# pressure-balloon.net
KiCad netlist of a schematic drawn in EAGLE
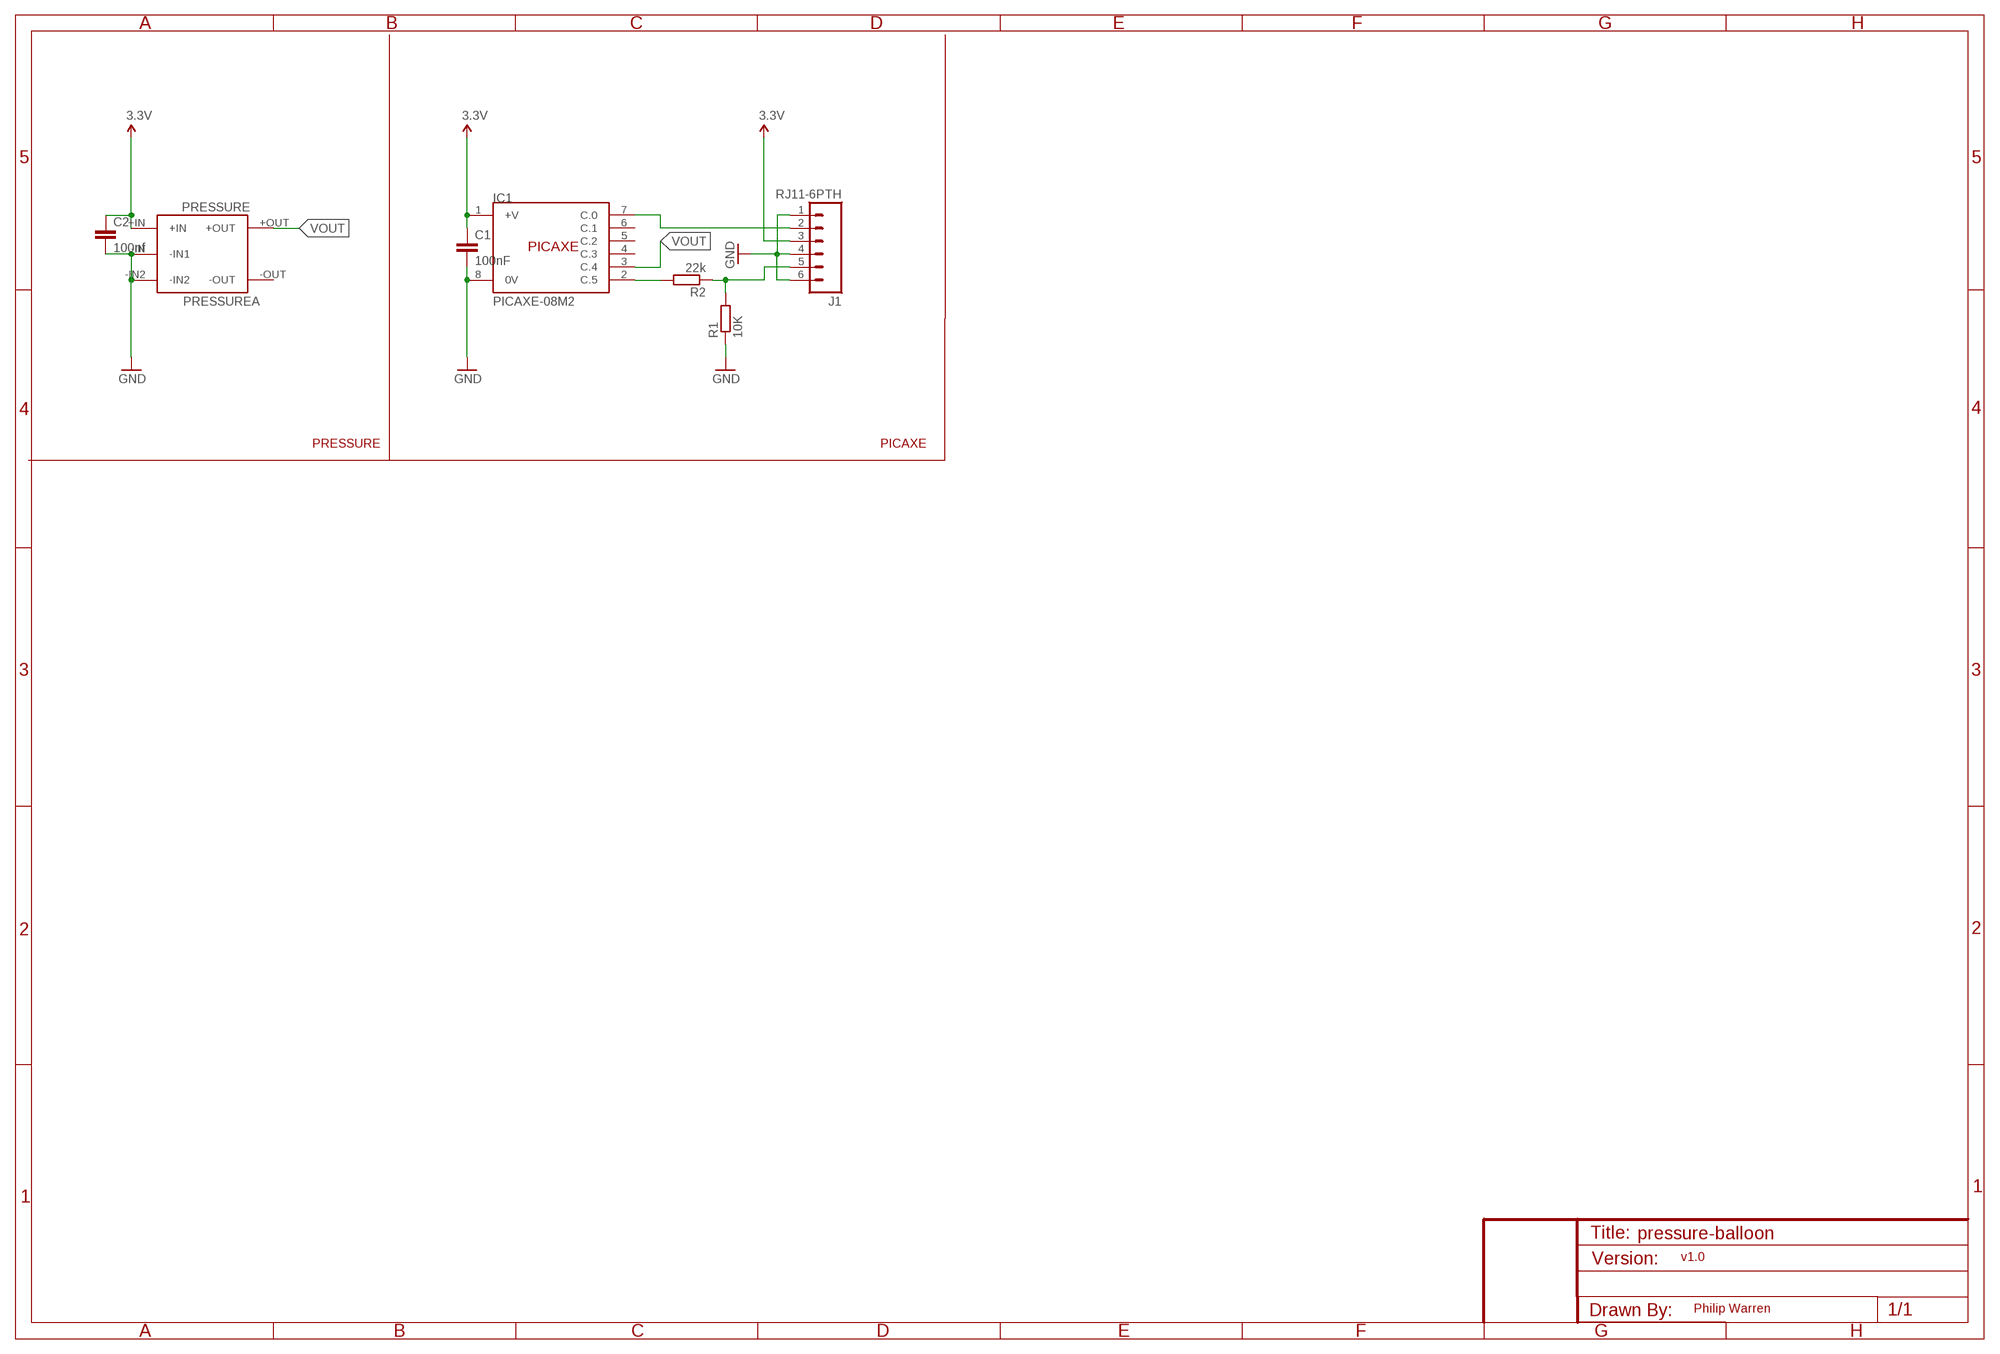
[diagram p0: schematic, sheet 1]

(export (version "E")
  (design (tool "Eeschema 10.0.6"))
  (components
    (comp (ref "C1")
      (value "100nF")
      (footprint "eagle-import:0805")
      (libsource (lib "eagle-import") (part "CAP0805"))
    )
    (comp (ref "C2")
      (value "100nf")
      (footprint "eagle-import:0805")
      (libsource (lib "eagle-import") (part "CAP0805"))
    )
    (comp (ref "IC1")
      (value "PICAXE-08M2")
      (footprint "eagle-import:SOIC8")
      (libsource (lib "eagle-import") (part "PICAXE-08M2"))
    )
    (comp (ref "J1")
      (value "RJ11-6PTH")
      (footprint "eagle-import:RJ11-6")
      (libsource (lib "eagle-import") (part "RJ11-6PTH"))
    )
    (comp (ref "PRESSURE")
      (value "PRESSUREA")
      (footprint "eagle-import:PRESSURE")
      (libsource (lib "eagle-import") (part "PRESSUREA"))
    )
    (comp (ref "R1")
      (value "10K")
      (footprint "eagle-import:R0805")
      (libsource (lib "eagle-import") (part "R-EU_R0805"))
    )
    (comp (ref "R2")
      (value "22k")
      (footprint "eagle-import:R0805")
      (libsource (lib "eagle-import") (part "R-EU_R0805"))
    )
  )
  (nets
    (net (code "1") (name "3.3V") (class "Default")
      (node (ref "C1") (pin "1") (pinfunction "1_1") (pintype "passive"))
      (node (ref "C2") (pin "1") (pinfunction "1_1") (pintype "passive"))
      (node (ref "IC1") (pin "1") (pinfunction "+V_1") (pintype "power_in"))
      (node (ref "J1") (pin "3") (pinfunction "3_3") (pintype "passive"))
      (node (ref "PRESSURE") (pin "+IN") (pinfunction "+IN_+IN") (pintype "bidirectional"))
    )
    (net (code "2") (name "GND") (class "Default")
      (node (ref "C1") (pin "2") (pinfunction "2_2") (pintype "passive"))
      (node (ref "C2") (pin "2") (pinfunction "2_2") (pintype "passive"))
      (node (ref "IC1") (pin "8") (pinfunction "0V_8") (pintype "power_in"))
      (node (ref "J1") (pin "1") (pinfunction "1_1") (pintype "passive"))
      (node (ref "J1") (pin "4") (pinfunction "4_4") (pintype "passive"))
      (node (ref "J1") (pin "6") (pinfunction "6_6") (pintype "passive"))
      (node (ref "PRESSURE") (pin "-IN") (pinfunction "-IN1_-IN") (pintype "bidirectional"))
      (node (ref "PRESSURE") (pin "-IN2") (pinfunction "-IN2_-IN2") (pintype "bidirectional"))
      (node (ref "R1") (pin "1") (pinfunction "1_1") (pintype "passive"))
    )
    (net (code "3") (name "Net-(IC1-C.0)") (class "Default")
      (node (ref "IC1") (pin "7") (pinfunction "C.0_7") (pintype "bidirectional"))
      (node (ref "J1") (pin "2") (pinfunction "2_2") (pintype "passive"))
    )
    (net (code "4") (name "Net-(IC1-C.5)") (class "Default")
      (node (ref "IC1") (pin "2") (pinfunction "C.5_2") (pintype "bidirectional"))
      (node (ref "R2") (pin "2") (pinfunction "2_2") (pintype "passive"))
    )
    (net (code "5") (name "Net-(J1-Pad5)") (class "Default")
      (node (ref "J1") (pin "5") (pinfunction "5_5") (pintype "passive"))
      (node (ref "R1") (pin "2") (pinfunction "2_2") (pintype "passive"))
      (node (ref "R2") (pin "1") (pinfunction "1_1") (pintype "passive"))
    )
    (net (code "6") (name "VOUT") (class "Default")
      (node (ref "IC1") (pin "3") (pinfunction "C.4_3") (pintype "bidirectional"))
      (node (ref "PRESSURE") (pin "+OUT") (pinfunction "+OUT_+OUT") (pintype "bidirectional"))
    )
    (net (code "7") (name "unconnected-(IC1-C.1-Pad6)") (class "Default")
      (node (ref "IC1") (pin "6") (pinfunction "C.1_6") (pintype "bidirectional"))
    )
    (net (code "8") (name "unconnected-(IC1-C.2-Pad5)") (class "Default")
      (node (ref "IC1") (pin "5") (pinfunction "C.2_5") (pintype "bidirectional"))
    )
    (net (code "9") (name "unconnected-(IC1-C.3-Pad4)") (class "Default")
      (node (ref "IC1") (pin "4") (pinfunction "C.3_4") (pintype "bidirectional"))
    )
    (net (code "10") (name "unconnected-(PRESSURE-Pad-OUT)") (class "Default")
      (node (ref "PRESSURE") (pin "-OUT") (pinfunction "-OUT_-OUT") (pintype "bidirectional"))
    )
  )
)
